# SCH_Voltage_Regulator_2023-12-21.net
KiCad netlist of a schematic drawn in EasyEDA
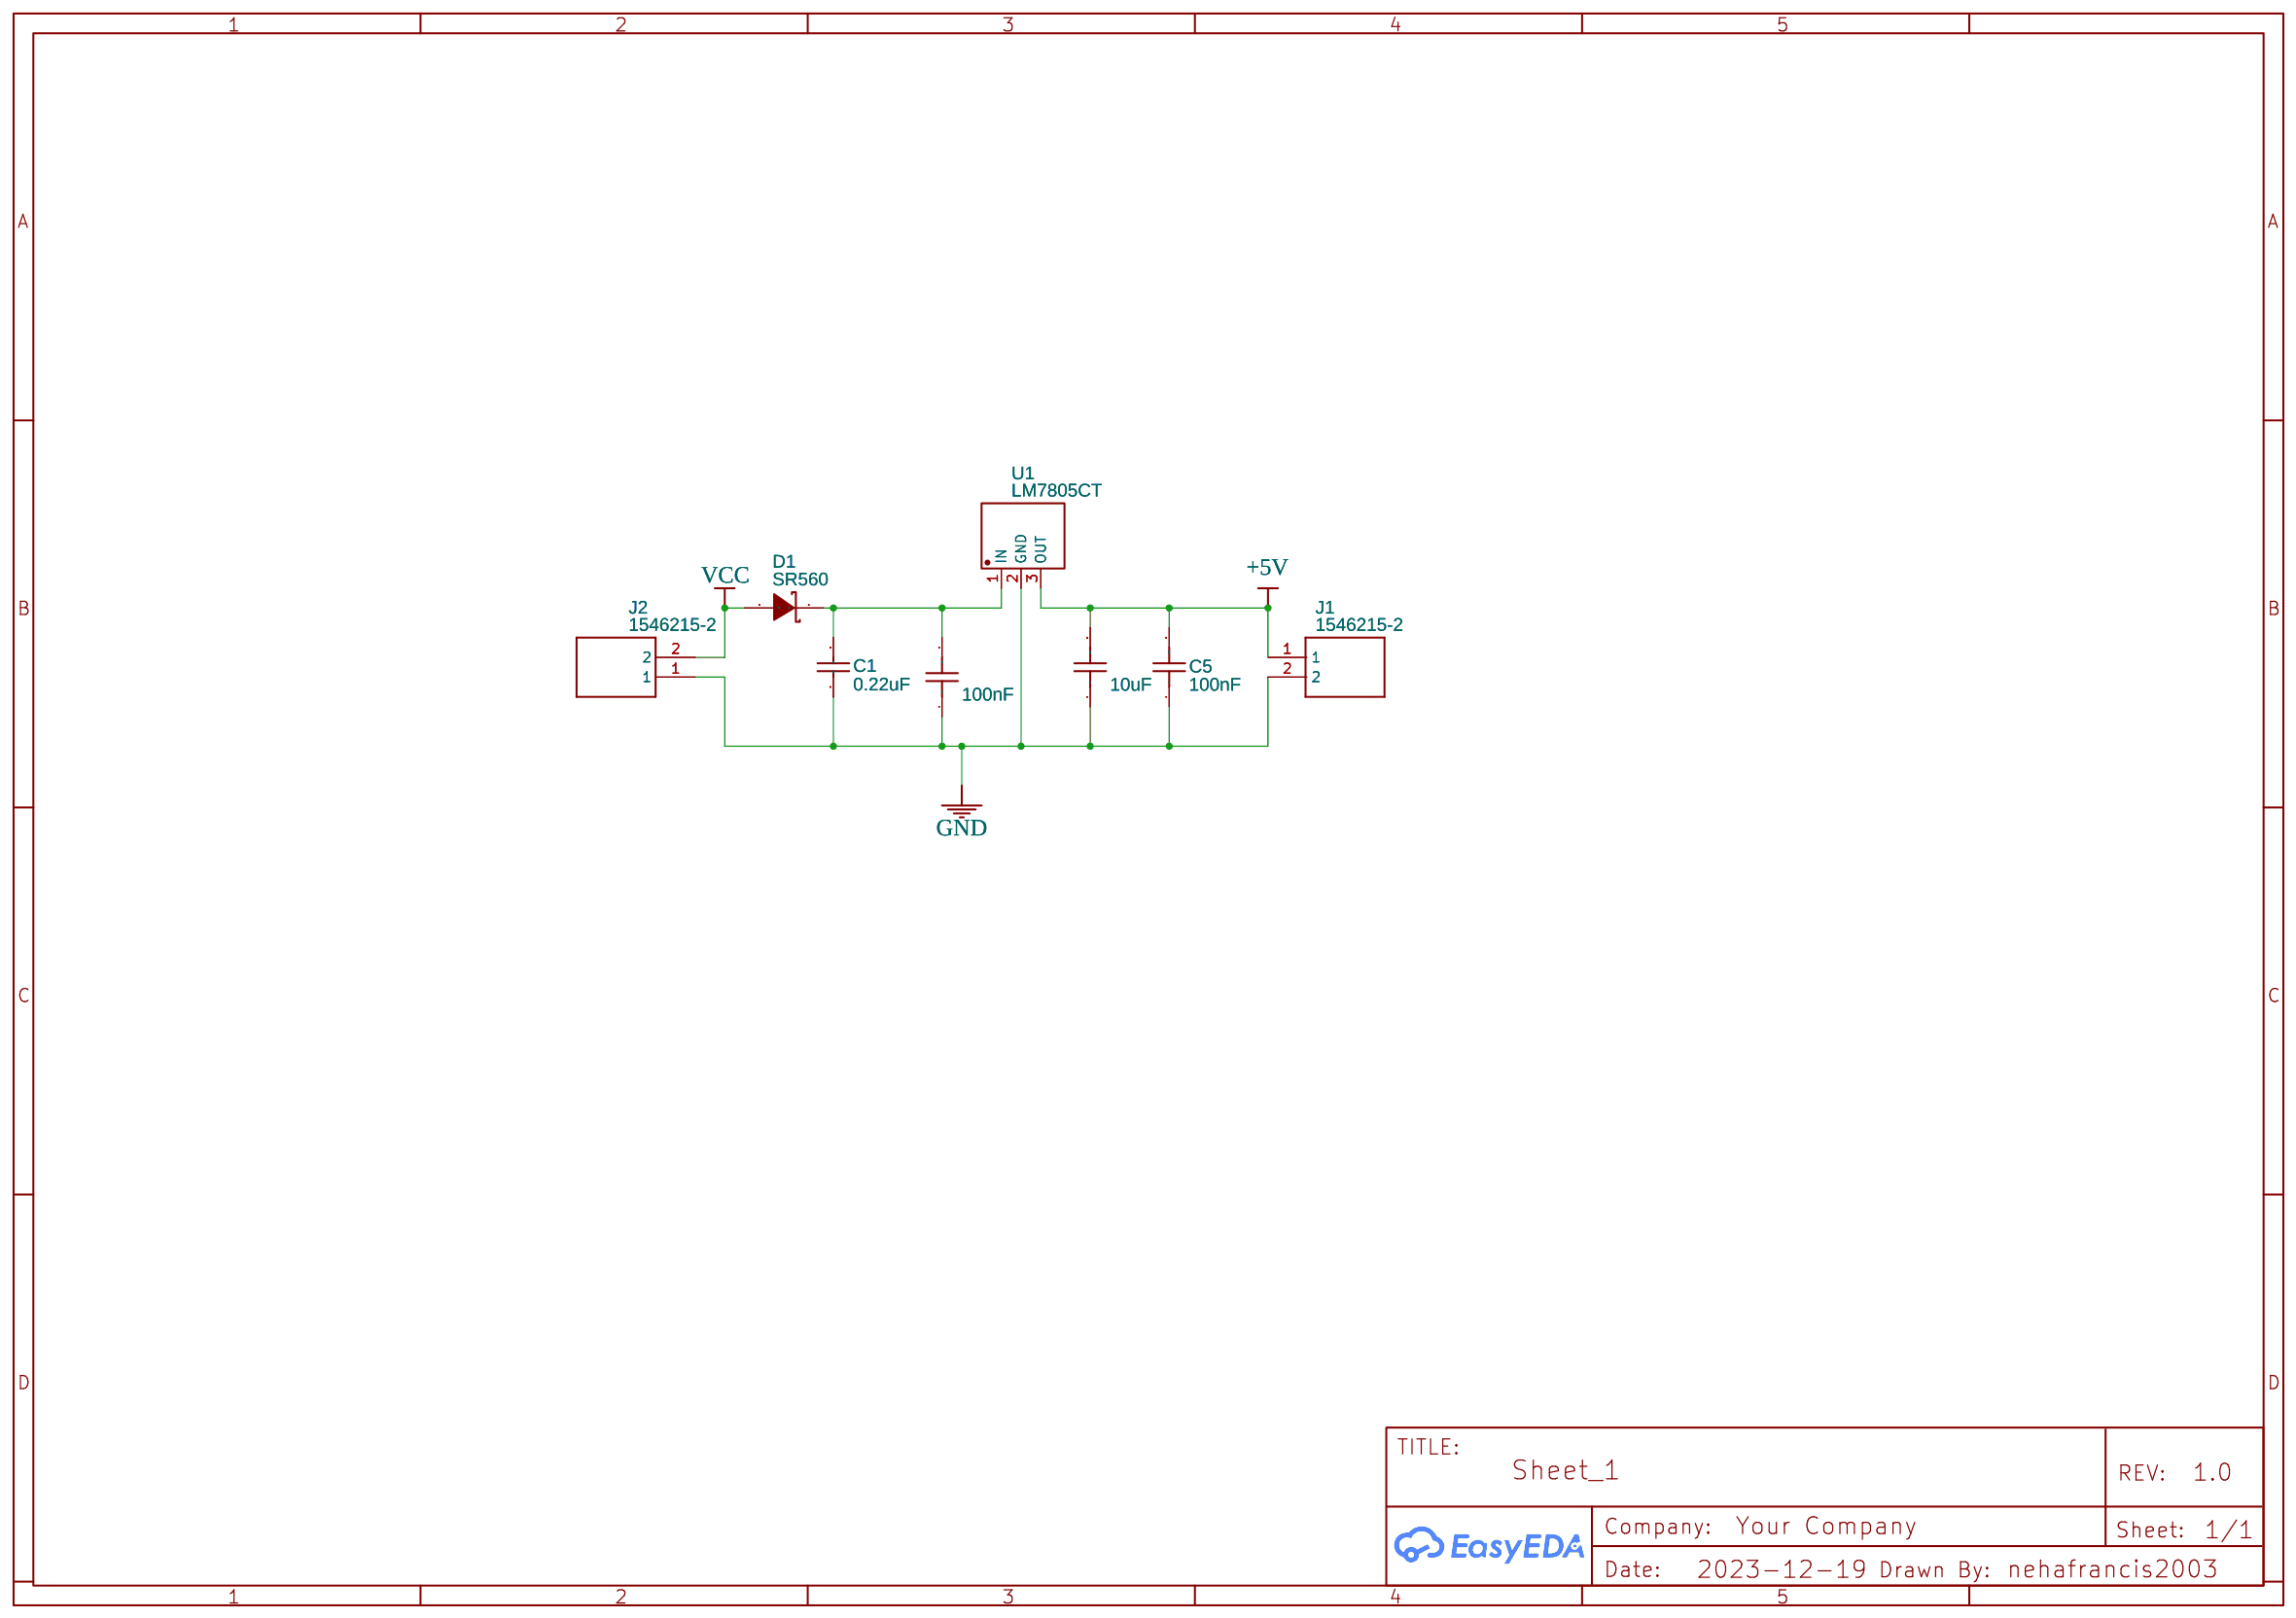
[diagram p0: schematic sheet]

(export (version "E")
  (design (tool "Eeschema 10.0.6"))
  (components
    (comp (ref "C1")
      (value "0.22uF")
      (fields (field (name "Manufacturer Part") "CT4-0805Y224M500") (field (name "Manufacturer") "ReliaPro"))
      (libsource (lib "") (part "CT4-0805Y224M500"))
    )
    (comp (ref "C2")
      (value "100nF")
      (fields
        (field (name "Manufacturer Part") "CT4G-0805-2X1-50V-0.1μF-K")
        (field (name "Manufacturer") "TORCH(火炬)")
      )
      (libsource (lib "") (part "CT4G-0805-2X1-50V-0.1UF-K"))
    )
    (comp (ref "C5")
      (value "100nF")
      (fields
        (field (name "Manufacturer Part") "CT4G-0805-2X1-50V-0.1μF-K")
        (field (name "Manufacturer") "TORCH(火炬)")
      )
      (libsource (lib "") (part "CT4G-0805-2X1-50V-0.1UF-K"))
    )
    (comp (ref "C6")
      (value "10uF")
      (fields (field (name "Manufacturer Part") "FK11X7R1C106MR006") (field (name "Manufacturer") "TDK"))
      (libsource (lib "") (part "FK11X7R1C106MR006"))
    )
    (comp (ref "D1")
      (value "SR560")
      (fields (field (name "Manufacturer") "MDD"))
      (libsource (lib "") (part "SR560"))
    )
    (comp (ref "J1") (value "1546215-2") (libsource (lib "") (part "1546215-2_1")))
    (comp (ref "J2") (value "1546215-2") (libsource (lib "") (part "1546215-2")))
    (comp (ref "U1")
      (value "LM7805CT")
      (fields (field (name "Manufacturer") "onsemi(安森美)"))
      (libsource (lib "") (part "LM7805CT"))
    )
  )
  (nets
    (net (code "1") (name "+5V") (class "Default")
      (node (ref "C5") (pin "2") (pinfunction "2_2") (pintype "unspecified"))
      (node (ref "C6") (pin "2") (pinfunction "2_2") (pintype "unspecified"))
      (node (ref "J1") (pin "1") (pinfunction "1_1") (pintype "bidirectional"))
      (node (ref "U1") (pin "3") (pinfunction "OUT_3") (pintype "unspecified"))
    )
    (net (code "2") (name "GND") (class "Default")
      (node (ref "C1") (pin "2") (pinfunction "2_2") (pintype "input"))
      (node (ref "C2") (pin "1") (pinfunction "1_1") (pintype "unspecified"))
      (node (ref "C5") (pin "1") (pinfunction "1_1") (pintype "unspecified"))
      (node (ref "C6") (pin "1") (pinfunction "1_1") (pintype "unspecified"))
      (node (ref "J1") (pin "2") (pinfunction "2_2") (pintype "bidirectional"))
      (node (ref "J2") (pin "1") (pinfunction "1_1") (pintype "bidirectional"))
      (node (ref "U1") (pin "2") (pinfunction "GND_2") (pintype "unspecified"))
    )
    (net (code "3") (name "Net-(D1-K)") (class "Default")
      (node (ref "C1") (pin "1") (pinfunction "1_1") (pintype "input"))
      (node (ref "C2") (pin "2") (pinfunction "2_2") (pintype "unspecified"))
      (node (ref "D1") (pin "2") (pinfunction "K_2") (pintype "unspecified"))
      (node (ref "U1") (pin "1") (pinfunction "IN_1") (pintype "unspecified"))
    )
    (net (code "4") (name "VCC") (class "Default")
      (node (ref "D1") (pin "1") (pinfunction "A_1") (pintype "unspecified"))
      (node (ref "J2") (pin "2") (pinfunction "2_2") (pintype "bidirectional"))
    )
  )
)
